# rgb-matrix-backpack-3-test.net
KiCad netlist of a schematic drawn in EAGLE
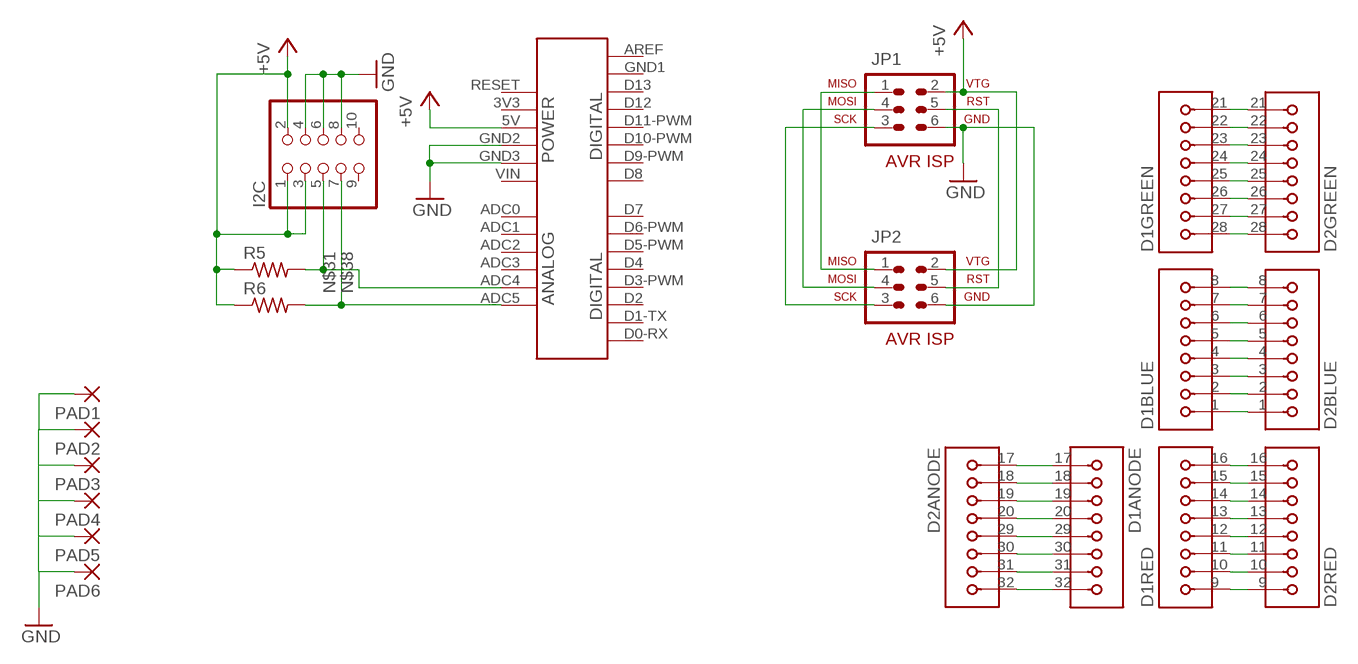
[diagram p0: schematic, sheet 1]

(export (version "E")
  (design (tool "Eeschema 10.0.6"))
  (components
    (comp (ref "D1")
      (value "60MM-8X8-RGB-LED-ARRAY")
      (footprint "eagle-import:60MM-8X8-RGB-MATRIX")
      (libsource (lib "eagle-import") (part "60MM-8X8-RGB-LED-ARRAY"))
    )
    (comp (ref "D2")
      (value "60MM-8X8-RGB-LED-ARRAY")
      (footprint "eagle-import:60MM-8X8-RGB-MATRIX")
      (libsource (lib "eagle-import") (part "60MM-8X8-RGB-LED-ARRAY"))
    )
    (comp (ref "I2C")
      (value "PINHD-2X5_2.54-90°")
      (footprint "eagle-import:2X05_90")
      (libsource (lib "eagle-import") (part "PINHD-2X5_2.54-90°"))
    )
    (comp (ref "JP1")
      (value "AVR-ISP-6")
      (footprint "eagle-import:AVR-ISP-6")
      (libsource (lib "eagle-import") (part "AVR-ISP-6"))
    )
    (comp (ref "JP2")
      (value "AVR-ISP-6")
      (footprint "eagle-import:AVR-ISP-6")
      (libsource (lib "eagle-import") (part "AVR-ISP-6"))
    )
    (comp (ref "PAD1")
      (value "1,6/0,8")
      (footprint "eagle-import:1,6_0,8")
      (libsource (lib "eagle-import") (part "1,6/0,8"))
    )
    (comp (ref "PAD2")
      (value "1,6/0,8")
      (footprint "eagle-import:1,6_0,8")
      (libsource (lib "eagle-import") (part "1,6/0,8"))
    )
    (comp (ref "PAD3")
      (value "1,6/0,8")
      (footprint "eagle-import:1,6_0,8")
      (libsource (lib "eagle-import") (part "1,6/0,8"))
    )
    (comp (ref "PAD4")
      (value "1,6/0,8")
      (footprint "eagle-import:1,6_0,8")
      (libsource (lib "eagle-import") (part "1,6/0,8"))
    )
    (comp (ref "PAD5")
      (value "1,6/0,8")
      (footprint "eagle-import:1,6_0,8")
      (libsource (lib "eagle-import") (part "1,6/0,8"))
    )
    (comp (ref "PAD6")
      (value "1,6/0,8")
      (footprint "eagle-import:1,6_0,8")
      (libsource (lib "eagle-import") (part "1,6/0,8"))
    )
    (comp (ref "R5")
      (value "R-US_R0603")
      (footprint "eagle-import:R0603")
      (libsource (lib "eagle-import") (part "R-US_R0603"))
    )
    (comp (ref "R6")
      (value "R-US_R0603")
      (footprint "eagle-import:R0603")
      (libsource (lib "eagle-import") (part "R-US_R0603"))
    )
    (comp (ref "SHIELD1")
      (value "2009")
      (footprint "eagle-import:2009")
      (libsource (lib "eagle-import") (part "2009"))
    )
  )
  (nets
    (net (code "1") (name "+5V") (class "Default")
      (node (ref "I2C") (pin "1") (pinfunction "1_1") (pintype "passive"))
      (node (ref "I2C") (pin "2") (pinfunction "2_2") (pintype "passive"))
      (node (ref "I2C") (pin "3") (pinfunction "3_3") (pintype "passive"))
      (node (ref "JP1") (pin "2") (pinfunction "2_2") (pintype "passive"))
      (node (ref "JP2") (pin "2") (pinfunction "2_2") (pintype "passive"))
      (node (ref "R5") (pin "1") (pinfunction "1_1") (pintype "passive"))
      (node (ref "R6") (pin "1") (pinfunction "1_1") (pintype "passive"))
      (node (ref "SHIELD1") (pin "5V") (pinfunction "5V_5V") (pintype "bidirectional"))
    )
    (net (code "2") (name "/N$31") (class "Default")
      (node (ref "I2C") (pin "5") (pinfunction "5_5") (pintype "passive"))
      (node (ref "R5") (pin "2") (pinfunction "2_2") (pintype "passive"))
      (node (ref "SHIELD1") (pin "ADC4") (pinfunction "ADC4_ADC4") (pintype "bidirectional"))
    )
    (net (code "3") (name "/N$38") (class "Default")
      (node (ref "I2C") (pin "7") (pinfunction "7_7") (pintype "passive"))
      (node (ref "R6") (pin "2") (pinfunction "2_2") (pintype "passive"))
      (node (ref "SHIELD1") (pin "ADC5") (pinfunction "ADC5_ADC5") (pintype "bidirectional"))
    )
    (net (code "4") (name "GND") (class "Default")
      (node (ref "I2C") (pin "4") (pinfunction "4_4") (pintype "passive"))
      (node (ref "I2C") (pin "6") (pinfunction "6_6") (pintype "passive"))
      (node (ref "I2C") (pin "8") (pinfunction "8_8") (pintype "passive"))
      (node (ref "JP1") (pin "6") (pinfunction "6_6") (pintype "passive"))
      (node (ref "JP2") (pin "6") (pinfunction "6_6") (pintype "passive"))
      (node (ref "PAD1") (pin "1") (pinfunction "P_1") (pintype "passive"))
      (node (ref "PAD2") (pin "1") (pinfunction "P_1") (pintype "passive"))
      (node (ref "PAD3") (pin "1") (pinfunction "P_1") (pintype "passive"))
      (node (ref "PAD4") (pin "1") (pinfunction "P_1") (pintype "passive"))
      (node (ref "PAD5") (pin "1") (pinfunction "P_1") (pintype "passive"))
      (node (ref "PAD6") (pin "1") (pinfunction "P_1") (pintype "passive"))
      (node (ref "SHIELD1") (pin "GND2") (pinfunction "GND2_GND2") (pintype "bidirectional"))
      (node (ref "SHIELD1") (pin "GND3") (pinfunction "GND3_GND3") (pintype "bidirectional"))
    )
    (net (code "5") (name "Net-(D1-Pad1)") (class "Default")
      (node (ref "D1") (pin "1") (pinfunction "1_1") (pintype "bidirectional"))
      (node (ref "D2") (pin "1") (pinfunction "1_1") (pintype "bidirectional"))
    )
    (net (code "6") (name "Net-(D1-Pad2)") (class "Default")
      (node (ref "D1") (pin "2") (pinfunction "2_2") (pintype "bidirectional"))
      (node (ref "D2") (pin "2") (pinfunction "2_2") (pintype "bidirectional"))
    )
    (net (code "7") (name "Net-(D1-Pad3)") (class "Default")
      (node (ref "D1") (pin "3") (pinfunction "3_3") (pintype "bidirectional"))
      (node (ref "D2") (pin "3") (pinfunction "3_3") (pintype "bidirectional"))
    )
    (net (code "8") (name "Net-(D1-Pad4)") (class "Default")
      (node (ref "D1") (pin "4") (pinfunction "4_4") (pintype "bidirectional"))
      (node (ref "D2") (pin "4") (pinfunction "4_4") (pintype "bidirectional"))
    )
    (net (code "9") (name "Net-(D1-Pad5)") (class "Default")
      (node (ref "D1") (pin "5") (pinfunction "5_5") (pintype "bidirectional"))
      (node (ref "D2") (pin "5") (pinfunction "5_5") (pintype "bidirectional"))
    )
    (net (code "10") (name "Net-(D1-Pad6)") (class "Default")
      (node (ref "D1") (pin "6") (pinfunction "6_6") (pintype "bidirectional"))
      (node (ref "D2") (pin "6") (pinfunction "6_6") (pintype "bidirectional"))
    )
    (net (code "11") (name "Net-(D1-Pad7)") (class "Default")
      (node (ref "D1") (pin "7") (pinfunction "7_7") (pintype "bidirectional"))
      (node (ref "D2") (pin "7") (pinfunction "7_7") (pintype "bidirectional"))
    )
    (net (code "12") (name "Net-(D1-Pad8)") (class "Default")
      (node (ref "D1") (pin "8") (pinfunction "8_8") (pintype "bidirectional"))
      (node (ref "D2") (pin "8") (pinfunction "8_8") (pintype "bidirectional"))
    )
    (net (code "13") (name "Net-(D1A-1)") (class "Default")
      (node (ref "D1") (pin "17") (pinfunction "1_17") (pintype "bidirectional"))
      (node (ref "D2") (pin "17") (pinfunction "1_17") (pintype "bidirectional"))
    )
    (net (code "14") (name "Net-(D1A-2)") (class "Default")
      (node (ref "D1") (pin "18") (pinfunction "2_18") (pintype "bidirectional"))
      (node (ref "D2") (pin "18") (pinfunction "2_18") (pintype "bidirectional"))
    )
    (net (code "15") (name "Net-(D1A-3)") (class "Default")
      (node (ref "D1") (pin "19") (pinfunction "3_19") (pintype "bidirectional"))
      (node (ref "D2") (pin "19") (pinfunction "3_19") (pintype "bidirectional"))
    )
    (net (code "16") (name "Net-(D1A-4)") (class "Default")
      (node (ref "D1") (pin "20") (pinfunction "4_20") (pintype "bidirectional"))
      (node (ref "D2") (pin "20") (pinfunction "4_20") (pintype "bidirectional"))
    )
    (net (code "17") (name "Net-(D1A-5)") (class "Default")
      (node (ref "D1") (pin "29") (pinfunction "5_29") (pintype "bidirectional"))
      (node (ref "D2") (pin "29") (pinfunction "5_29") (pintype "bidirectional"))
    )
    (net (code "18") (name "Net-(D1A-6)") (class "Default")
      (node (ref "D1") (pin "30") (pinfunction "6_30") (pintype "bidirectional"))
      (node (ref "D2") (pin "30") (pinfunction "6_30") (pintype "bidirectional"))
    )
    (net (code "19") (name "Net-(D1A-7)") (class "Default")
      (node (ref "D1") (pin "31") (pinfunction "7_31") (pintype "bidirectional"))
      (node (ref "D2") (pin "31") (pinfunction "7_31") (pintype "bidirectional"))
    )
    (net (code "20") (name "Net-(D1A-8)") (class "Default")
      (node (ref "D1") (pin "32") (pinfunction "8_32") (pintype "bidirectional"))
      (node (ref "D2") (pin "32") (pinfunction "8_32") (pintype "bidirectional"))
    )
    (net (code "21") (name "Net-(D1C-1)") (class "Default")
      (node (ref "D1") (pin "28") (pinfunction "1_28") (pintype "bidirectional"))
      (node (ref "D2") (pin "28") (pinfunction "1_28") (pintype "bidirectional"))
    )
    (net (code "22") (name "Net-(D1C-2)") (class "Default")
      (node (ref "D1") (pin "27") (pinfunction "2_27") (pintype "bidirectional"))
      (node (ref "D2") (pin "27") (pinfunction "2_27") (pintype "bidirectional"))
    )
    (net (code "23") (name "Net-(D1C-3)") (class "Default")
      (node (ref "D1") (pin "26") (pinfunction "3_26") (pintype "bidirectional"))
      (node (ref "D2") (pin "26") (pinfunction "3_26") (pintype "bidirectional"))
    )
    (net (code "24") (name "Net-(D1C-4)") (class "Default")
      (node (ref "D1") (pin "25") (pinfunction "4_25") (pintype "bidirectional"))
      (node (ref "D2") (pin "25") (pinfunction "4_25") (pintype "bidirectional"))
    )
    (net (code "25") (name "Net-(D1C-5)") (class "Default")
      (node (ref "D1") (pin "24") (pinfunction "5_24") (pintype "bidirectional"))
      (node (ref "D2") (pin "24") (pinfunction "5_24") (pintype "bidirectional"))
    )
    (net (code "26") (name "Net-(D1C-6)") (class "Default")
      (node (ref "D1") (pin "23") (pinfunction "6_23") (pintype "bidirectional"))
      (node (ref "D2") (pin "23") (pinfunction "6_23") (pintype "bidirectional"))
    )
    (net (code "27") (name "Net-(D1C-7)") (class "Default")
      (node (ref "D1") (pin "22") (pinfunction "7_22") (pintype "bidirectional"))
      (node (ref "D2") (pin "22") (pinfunction "7_22") (pintype "bidirectional"))
    )
    (net (code "28") (name "Net-(D1C-8)") (class "Default")
      (node (ref "D1") (pin "21") (pinfunction "8_21") (pintype "bidirectional"))
      (node (ref "D2") (pin "21") (pinfunction "8_21") (pintype "bidirectional"))
    )
    (net (code "29") (name "Net-(D1D-1)") (class "Default")
      (node (ref "D1") (pin "9") (pinfunction "1_9") (pintype "bidirectional"))
      (node (ref "D2") (pin "9") (pinfunction "1_9") (pintype "bidirectional"))
    )
    (net (code "30") (name "Net-(D1D-2)") (class "Default")
      (node (ref "D1") (pin "10") (pinfunction "2_10") (pintype "bidirectional"))
      (node (ref "D2") (pin "10") (pinfunction "2_10") (pintype "bidirectional"))
    )
    (net (code "31") (name "Net-(D1D-3)") (class "Default")
      (node (ref "D1") (pin "11") (pinfunction "3_11") (pintype "bidirectional"))
      (node (ref "D2") (pin "11") (pinfunction "3_11") (pintype "bidirectional"))
    )
    (net (code "32") (name "Net-(D1D-4)") (class "Default")
      (node (ref "D1") (pin "12") (pinfunction "4_12") (pintype "bidirectional"))
      (node (ref "D2") (pin "12") (pinfunction "4_12") (pintype "bidirectional"))
    )
    (net (code "33") (name "Net-(D1D-5)") (class "Default")
      (node (ref "D1") (pin "13") (pinfunction "5_13") (pintype "bidirectional"))
      (node (ref "D2") (pin "13") (pinfunction "5_13") (pintype "bidirectional"))
    )
    (net (code "34") (name "Net-(D1D-6)") (class "Default")
      (node (ref "D1") (pin "14") (pinfunction "6_14") (pintype "bidirectional"))
      (node (ref "D2") (pin "14") (pinfunction "6_14") (pintype "bidirectional"))
    )
    (net (code "35") (name "Net-(D1D-7)") (class "Default")
      (node (ref "D1") (pin "15") (pinfunction "7_15") (pintype "bidirectional"))
      (node (ref "D2") (pin "15") (pinfunction "7_15") (pintype "bidirectional"))
    )
    (net (code "36") (name "Net-(D1D-8)") (class "Default")
      (node (ref "D1") (pin "16") (pinfunction "8_16") (pintype "bidirectional"))
      (node (ref "D2") (pin "16") (pinfunction "8_16") (pintype "bidirectional"))
    )
    (net (code "37") (name "Net-(JP1-Pad1)") (class "Default")
      (node (ref "JP1") (pin "1") (pinfunction "1_1") (pintype "passive"))
      (node (ref "JP2") (pin "1") (pinfunction "1_1") (pintype "passive"))
    )
    (net (code "38") (name "Net-(JP1-Pad3)") (class "Default")
      (node (ref "JP1") (pin "3") (pinfunction "3_3") (pintype "passive"))
      (node (ref "JP2") (pin "3") (pinfunction "3_3") (pintype "passive"))
    )
    (net (code "39") (name "Net-(JP1-Pad4)") (class "Default")
      (node (ref "JP1") (pin "4") (pinfunction "4_4") (pintype "passive"))
      (node (ref "JP2") (pin "4") (pinfunction "4_4") (pintype "passive"))
    )
    (net (code "40") (name "Net-(JP1-Pad5)") (class "Default")
      (node (ref "JP1") (pin "5") (pinfunction "5_5") (pintype "passive"))
      (node (ref "JP2") (pin "5") (pinfunction "5_5") (pintype "passive"))
    )
    (net (code "41") (name "unconnected-(I2C-Pad9)") (class "Default")
      (node (ref "I2C") (pin "9") (pinfunction "9_9") (pintype "passive"))
    )
    (net (code "42") (name "unconnected-(I2C-Pad10)") (class "Default")
      (node (ref "I2C") (pin "10") (pinfunction "10_10") (pintype "passive"))
    )
    (net (code "43") (name "unconnected-(SHIELD1-D0-PadD0-RX)") (class "Default")
      (node (ref "SHIELD1") (pin "D0-RX") (pinfunction "D0_D0-RX") (pintype "bidirectional"))
    )
    (net (code "44") (name "unconnected-(SHIELD1-D1-PadD1-TX)") (class "Default")
      (node (ref "SHIELD1") (pin "D1-TX") (pinfunction "D1_D1-TX") (pintype "bidirectional"))
    )
    (net (code "45") (name "unconnected-(SHIELD1-D3-PadD3-PWM)") (class "Default")
      (node (ref "SHIELD1") (pin "D3-PWM") (pinfunction "D3_D3-PWM") (pintype "bidirectional"))
    )
    (net (code "46") (name "unconnected-(SHIELD1-D5-PadD5-PWM)") (class "Default")
      (node (ref "SHIELD1") (pin "D5-PWM") (pinfunction "D5_D5-PWM") (pintype "bidirectional"))
    )
    (net (code "47") (name "unconnected-(SHIELD1-D6-PadD6-PWM)") (class "Default")
      (node (ref "SHIELD1") (pin "D6-PWM") (pinfunction "D6_D6-PWM") (pintype "bidirectional"))
    )
    (net (code "48") (name "unconnected-(SHIELD1-D9-PadD9-PWM)") (class "Default")
      (node (ref "SHIELD1") (pin "D9-PWM") (pinfunction "D9_D9-PWM") (pintype "bidirectional"))
    )
    (net (code "49") (name "unconnected-(SHIELD1-D10-PadD10-PWM)") (class "Default")
      (node (ref "SHIELD1") (pin "D10-PWM") (pinfunction "D10_D10-PWM") (pintype "bidirectional"))
    )
    (net (code "50") (name "unconnected-(SHIELD1-D11-PadD11-PWM)") (class "Default")
      (node (ref "SHIELD1") (pin "D11-PWM") (pinfunction "D11_D11-PWM") (pintype "bidirectional"))
    )
    (net (code "51") (name "unconnected-(SHIELD1-Pad3V3)") (class "Default")
      (node (ref "SHIELD1") (pin "3V3") (pinfunction "3V3_3V3") (pintype "bidirectional"))
    )
    (net (code "52") (name "unconnected-(SHIELD1-PadADC0)") (class "Default")
      (node (ref "SHIELD1") (pin "ADC0") (pinfunction "ADC0_ADC0") (pintype "bidirectional"))
    )
    (net (code "53") (name "unconnected-(SHIELD1-PadADC1)") (class "Default")
      (node (ref "SHIELD1") (pin "ADC1") (pinfunction "ADC1_ADC1") (pintype "bidirectional"))
    )
    (net (code "54") (name "unconnected-(SHIELD1-PadADC2)") (class "Default")
      (node (ref "SHIELD1") (pin "ADC2") (pinfunction "ADC2_ADC2") (pintype "bidirectional"))
    )
    (net (code "55") (name "unconnected-(SHIELD1-PadADC3)") (class "Default")
      (node (ref "SHIELD1") (pin "ADC3") (pinfunction "ADC3_ADC3") (pintype "bidirectional"))
    )
    (net (code "56") (name "unconnected-(SHIELD1-PadAREF)") (class "Default")
      (node (ref "SHIELD1") (pin "AREF") (pinfunction "AREF_AREF") (pintype "bidirectional"))
    )
    (net (code "57") (name "unconnected-(SHIELD1-PadD2)") (class "Default")
      (node (ref "SHIELD1") (pin "D2") (pinfunction "D2_D2") (pintype "bidirectional"))
    )
    (net (code "58") (name "unconnected-(SHIELD1-PadD4)") (class "Default")
      (node (ref "SHIELD1") (pin "D4") (pinfunction "D4_D4") (pintype "bidirectional"))
    )
    (net (code "59") (name "unconnected-(SHIELD1-PadD7)") (class "Default")
      (node (ref "SHIELD1") (pin "D7") (pinfunction "D7_D7") (pintype "bidirectional"))
    )
    (net (code "60") (name "unconnected-(SHIELD1-PadD8)") (class "Default")
      (node (ref "SHIELD1") (pin "D8") (pinfunction "D8_D8") (pintype "bidirectional"))
    )
    (net (code "61") (name "unconnected-(SHIELD1-PadD12)") (class "Default")
      (node (ref "SHIELD1") (pin "D12") (pinfunction "D12_D12") (pintype "bidirectional"))
    )
    (net (code "62") (name "unconnected-(SHIELD1-PadD13)") (class "Default")
      (node (ref "SHIELD1") (pin "D13") (pinfunction "D13_D13") (pintype "bidirectional"))
    )
    (net (code "63") (name "unconnected-(SHIELD1-PadGND1)") (class "Default")
      (node (ref "SHIELD1") (pin "GND1") (pinfunction "GND1_GND1") (pintype "bidirectional"))
    )
    (net (code "64") (name "unconnected-(SHIELD1-PadRESET)") (class "Default")
      (node (ref "SHIELD1") (pin "RESET") (pinfunction "RESET_RESET") (pintype "bidirectional"))
    )
    (net (code "65") (name "unconnected-(SHIELD1-PadVIN)") (class "Default")
      (node (ref "SHIELD1") (pin "VIN") (pinfunction "VIN_VIN") (pintype "bidirectional"))
    )
  )
)
